# Arduino_40hz_audio_and_led.net
KiCad netlist of a schematic drawn in EAGLE
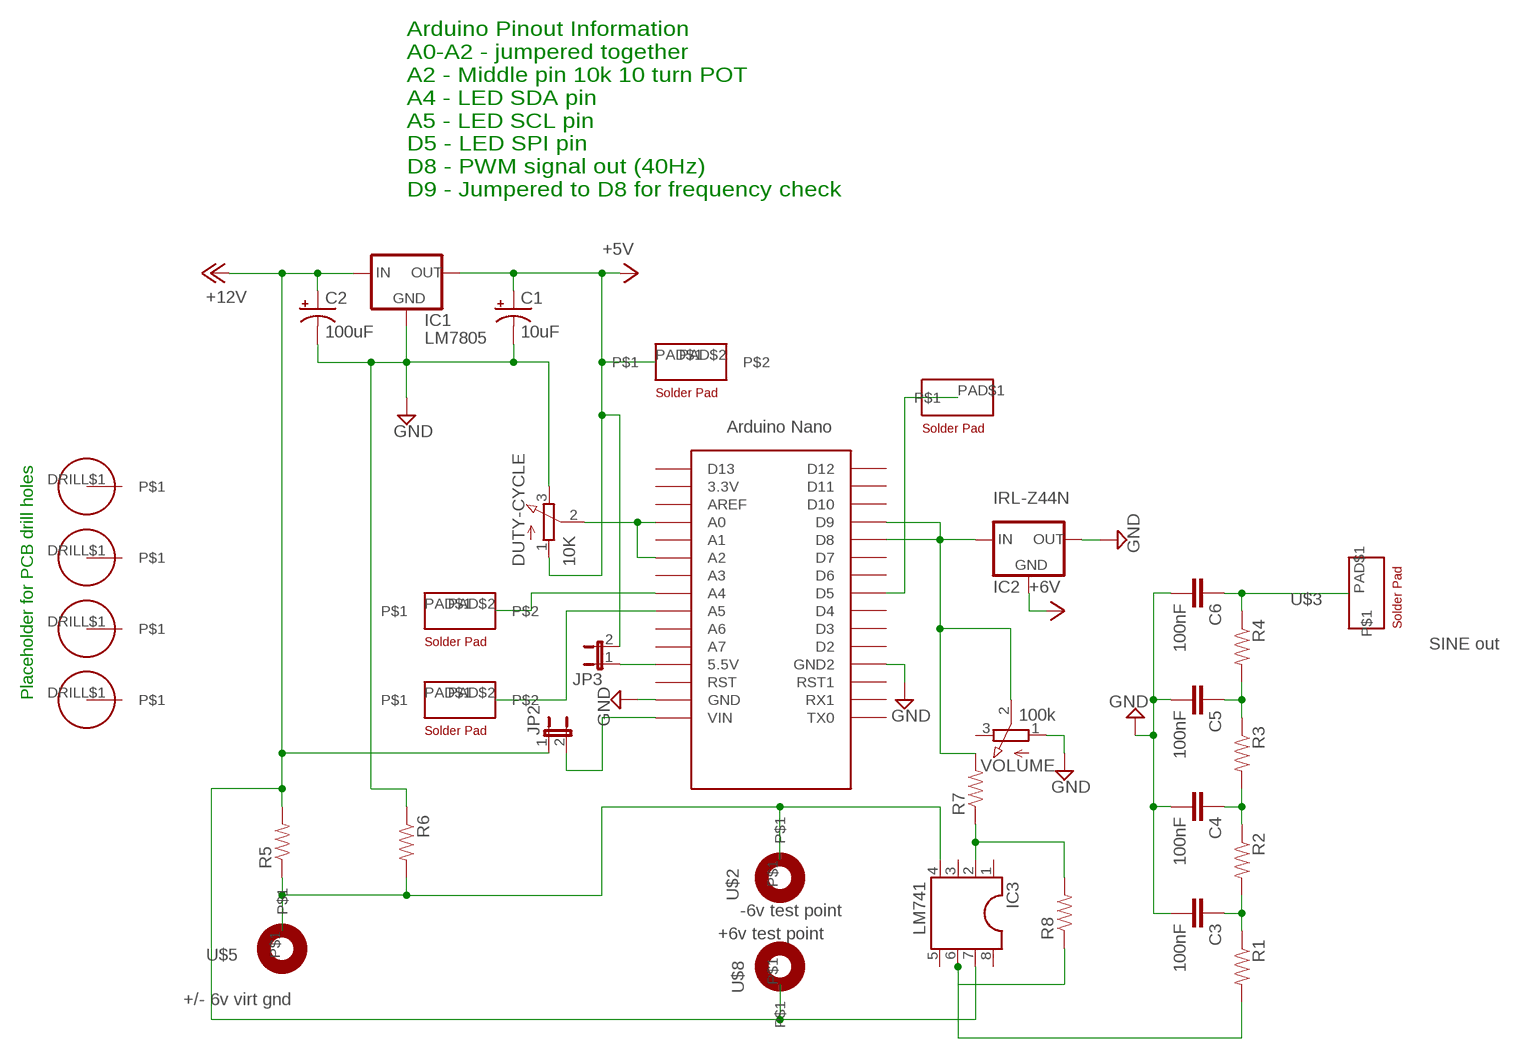
[diagram p0: schematic, sheet 1]

(export (version "E")
  (design (tool "Eeschema 10.0.6"))
  (components
    (comp (ref "C1")
      (value "10uF")
      (footprint "eagle-import:CAP-POLARIZED")
      (libsource (lib "eagle-import") (part "CAP-POLARIZED-RADIAL-2.5MM-25V-20%"))
    )
    (comp (ref "C2")
      (value "100uF")
      (footprint "eagle-import:CAP-POLARIZED")
      (libsource (lib "eagle-import") (part "CAP-POLARIZED-RADIAL-2.5MM-25V-20%"))
    )
    (comp (ref "C3")
      (value "100nF")
      (footprint "eagle-import:CAP-MEDIUM-MUPPET")
      (libsource (lib "eagle-import") (part "CAP-MEDIUM-MUPPET"))
    )
    (comp (ref "C4")
      (value "100nF")
      (footprint "eagle-import:CAP-MEDIUM-MUPPET")
      (libsource (lib "eagle-import") (part "CAP-MEDIUM-MUPPET"))
    )
    (comp (ref "C5")
      (value "100nF")
      (footprint "eagle-import:CAP-MEDIUM-MUPPET")
      (libsource (lib "eagle-import") (part "CAP-MEDIUM-MUPPET"))
    )
    (comp (ref "C6")
      (value "100nF")
      (footprint "eagle-import:CAP-MEDIUM-MUPPET")
      (libsource (lib "eagle-import") (part "CAP-MEDIUM-MUPPET"))
    )
    (comp (ref "DUTY-CYCLE")
      (value "10K")
      (footprint "eagle-import:POTENTIOMETER")
      (libsource (lib "eagle-import") (part "POTENTIOMETER"))
    )
    (comp (ref "IC1")
      (value "LM7805")
      (footprint "eagle-import:78XXL")
      (libsource (lib "eagle-import") (part "V_REG_78XXSIDE"))
    )
    (comp (ref "IC2")
      (value "IRL-Z44N")
      (footprint "eagle-import:78XXL")
      (libsource (lib "eagle-import") (part "V_REG_78XXSIDE"))
    )
    (comp (ref "IC3")
      (value "LM741")
      (footprint "eagle-import:DIL08")
      (libsource (lib "eagle-import") (part "DUAL-INLINE-8DIL08-2"))
    )
    (comp (ref "JP2")
      (value "JUMPER-JP1E")
      (footprint "eagle-import:JP1")
      (libsource (lib "eagle-import") (part "JUMPER-JP1E"))
    )
    (comp (ref "JP3")
      (value "JUMPER-JP1E")
      (footprint "eagle-import:JP1")
      (libsource (lib "eagle-import") (part "JUMPER-JP1E"))
    )
    (comp (ref "P+1")
      (value "+12V")
      (footprint "eagle-import:POWER-IN-PAD")
      (libsource (lib "eagle-import") (part "+12V"))
    )
    (comp (ref "P+2")
      (value "+5V")
      (footprint "eagle-import:POWER-IN-PAD")
      (libsource (lib "eagle-import") (part "+5V"))
    )
    (comp (ref "P+3")
      (value "+6V")
      (footprint "eagle-import:POWER-IN-PAD")
      (libsource (lib "eagle-import") (part "+6V"))
    )
    (comp (ref "R1")
      (value "RESISTORPTH-1/4W")
      (footprint "eagle-import:AXIAL-0.4")
      (libsource (lib "eagle-import") (part "RESISTORPTH-1/4W"))
    )
    (comp (ref "R2")
      (value "RESISTORPTH-1/4W")
      (footprint "eagle-import:AXIAL-0.4")
      (libsource (lib "eagle-import") (part "RESISTORPTH-1/4W"))
    )
    (comp (ref "R3")
      (value "RESISTORPTH-1/4W")
      (footprint "eagle-import:AXIAL-0.4")
      (libsource (lib "eagle-import") (part "RESISTORPTH-1/4W"))
    )
    (comp (ref "R4")
      (value "RESISTORPTH-1/4W")
      (footprint "eagle-import:AXIAL-0.4")
      (libsource (lib "eagle-import") (part "RESISTORPTH-1/4W"))
    )
    (comp (ref "R5")
      (value "RESISTORPTH-1/4W")
      (footprint "eagle-import:AXIAL-0.4")
      (libsource (lib "eagle-import") (part "RESISTORPTH-1/4W"))
    )
    (comp (ref "R6")
      (value "RESISTORPTH-1/4W")
      (footprint "eagle-import:AXIAL-0.4")
      (libsource (lib "eagle-import") (part "RESISTORPTH-1/4W"))
    )
    (comp (ref "R7")
      (value "RESISTORPTH-1/4W")
      (footprint "eagle-import:AXIAL-0.4")
      (libsource (lib "eagle-import") (part "RESISTORPTH-1/4W"))
    )
    (comp (ref "R8")
      (value "RESISTORPTH-1/4W")
      (footprint "eagle-import:AXIAL-0.4")
      (libsource (lib "eagle-import") (part "RESISTORPTH-1/4W"))
    )
    (comp (ref "U$1")
      (value "ARDUINO-NANO")
      (footprint "eagle-import:ARDUINO-NANO")
      (libsource (lib "eagle-import") (part "ARDUINO-NANO"))
    )
    (comp (ref "U$2")
      (value "-6v test point")
      (footprint "eagle-import:PROBE_POINT_1")
      (libsource (lib "eagle-import") (part "PROBE-POINTPROBE_POINT_1"))
    )
    (comp (ref "U$3")
      (value "SINE out")
      (footprint "eagle-import:PAD-1PIN-RECTANGLE-125MIL")
      (libsource (lib "eagle-import") (part "PAD-1PIN-RECTANGLE"))
    )
    (comp (ref "U$4")
      (value "PAD-2PIN-RECTANGLE")
      (footprint "eagle-import:PAD-2PIN-RECTANGLE-50MIL")
      (libsource (lib "eagle-import") (part "PAD-2PIN-RECTANGLE"))
    )
    (comp (ref "U$5")
      (value "+/- 6v virt gnd")
      (footprint "eagle-import:PROBE_POINT_1")
      (libsource (lib "eagle-import") (part "PROBE-POINTPROBE_POINT_1"))
    )
    (comp (ref "U$6")
      (value "PAD-2PIN-RECTANGLE")
      (footprint "eagle-import:PAD-2PIN-RECTANGLE-50MIL")
      (libsource (lib "eagle-import") (part "PAD-2PIN-RECTANGLE"))
    )
    (comp (ref "U$7")
      (value "PAD-2PIN-RECTANGLE")
      (footprint "eagle-import:PAD-2PIN-RECTANGLE-50MIL")
      (libsource (lib "eagle-import") (part "PAD-2PIN-RECTANGLE"))
    )
    (comp (ref "U$8")
      (value "+6v test point")
      (footprint "eagle-import:PROBE_POINT_1")
      (libsource (lib "eagle-import") (part "PROBE-POINTPROBE_POINT_1"))
    )
    (comp (ref "U$9")
      (value "PAD-1PIN-RECTANGLE")
      (footprint "eagle-import:PAD-1PIN-RECTANGLE-125MIL")
      (libsource (lib "eagle-import") (part "PAD-1PIN-RECTANGLE"))
    )
    (comp (ref "U$10")
      (value "DRILL-HOLE-4MM")
      (footprint "eagle-import:DRILL-HOLE-4MM")
      (libsource (lib "eagle-import") (part "DRILL-HOLE-4MM"))
    )
    (comp (ref "U$11")
      (value "DRILL-HOLE-4MM")
      (footprint "eagle-import:DRILL-HOLE-4MM")
      (libsource (lib "eagle-import") (part "DRILL-HOLE-4MM"))
    )
    (comp (ref "U$12")
      (value "DRILL-HOLE-4MM")
      (footprint "eagle-import:DRILL-HOLE-4MM")
      (libsource (lib "eagle-import") (part "DRILL-HOLE-4MM"))
    )
    (comp (ref "U$13")
      (value "DRILL-HOLE-4MM")
      (footprint "eagle-import:DRILL-HOLE-4MM")
      (libsource (lib "eagle-import") (part "DRILL-HOLE-4MM"))
    )
    (comp (ref "VOLUME")
      (value "100k")
      (footprint "eagle-import:POTENTIOMETER")
      (libsource (lib "eagle-import") (part "POTENTIOMETER"))
    )
  )
  (nets
    (net (code "1") (name "+5V") (class "Default")
      (node (ref "C1") (pin "1") (pinfunction "+_1") (pintype "passive"))
      (node (ref "DUTY-CYCLE") (pin "1") (pinfunction "A_1") (pintype "passive"))
      (node (ref "IC1") (pin "OUT") (pinfunction "OUT_OUT") (pintype "output"))
      (node (ref "IC2") (pin "GND") (pinfunction "GND_GND") (pintype "input"))
      (node (ref "JP3") (pin "2") (pinfunction "2_2") (pintype "passive"))
      (node (ref "P+2") (pin "VCC") (pinfunction "+5V_VCC") (pintype "power_in"))
      (node (ref "P+3") (pin "VCC") (pinfunction "+5V_VCC") (pintype "power_in"))
      (node (ref "U$7") (pin "PAD$1") (pinfunction "P$1_PAD$1") (pintype "bidirectional"))
    )
    (net (code "2") (name "+12V") (class "Default")
      (node (ref "C2") (pin "1") (pinfunction "+_1") (pintype "passive"))
      (node (ref "IC1") (pin "IN") (pinfunction "IN_IN") (pintype "input"))
      (node (ref "IC3") (pin "7") (pinfunction "7_7") (pintype "passive"))
      (node (ref "JP2") (pin "1") (pinfunction "1_1") (pintype "passive"))
      (node (ref "P+1") (pin "VCC") (pinfunction "+12V_VCC") (pintype "power_in"))
      (node (ref "R5") (pin "P$2") (pinfunction "2_P$2") (pintype "passive"))
      (node (ref "U$8") (pin "P$1") (pinfunction "P$1_P$1") (pintype "bidirectional"))
    )
    (net (code "3") (name "GND") (class "Default")
      (node (ref "C1") (pin "2") (pinfunction "-_2") (pintype "passive"))
      (node (ref "C2") (pin "2") (pinfunction "-_2") (pintype "passive"))
      (node (ref "C3") (pin "2") (pinfunction "2_2") (pintype "passive"))
      (node (ref "C4") (pin "2") (pinfunction "2_2") (pintype "passive"))
      (node (ref "C5") (pin "2") (pinfunction "2_2") (pintype "passive"))
      (node (ref "C6") (pin "2") (pinfunction "2_2") (pintype "passive"))
      (node (ref "DUTY-CYCLE") (pin "3") (pinfunction "E_3") (pintype "passive"))
      (node (ref "IC1") (pin "GND") (pinfunction "GND_GND") (pintype "input"))
      (node (ref "IC2") (pin "OUT") (pinfunction "OUT_OUT") (pintype "output"))
      (node (ref "R6") (pin "P$1") (pinfunction "1_P$1") (pintype "passive"))
      (node (ref "U$1") (pin "GND") (pinfunction "GND_GND") (pintype "bidirectional"))
      (node (ref "U$1") (pin "GND1") (pinfunction "GND2_GND1") (pintype "bidirectional"))
      (node (ref "VOLUME") (pin "1") (pinfunction "A_1") (pintype "passive"))
    )
    (net (code "4") (name "Net-(DUTY-CYCLE-S)") (class "Default")
      (node (ref "DUTY-CYCLE") (pin "2") (pinfunction "S_2") (pintype "passive"))
      (node (ref "U$1") (pin "A0") (pinfunction "A0_A0") (pintype "bidirectional"))
      (node (ref "U$1") (pin "A2") (pinfunction "A2_A2") (pintype "bidirectional"))
    )
    (net (code "5") (name "Net-(R1-1)") (class "Default")
      (node (ref "C3") (pin "1") (pinfunction "1_1") (pintype "passive"))
      (node (ref "R1") (pin "P$1") (pinfunction "1_P$1") (pintype "passive"))
      (node (ref "R2") (pin "P$2") (pinfunction "2_P$2") (pintype "passive"))
    )
    (net (code "6") (name "Net-(R1-2)") (class "Default")
      (node (ref "IC3") (pin "6") (pinfunction "6_6") (pintype "passive"))
      (node (ref "R1") (pin "P$2") (pinfunction "2_P$2") (pintype "passive"))
      (node (ref "R8") (pin "P$1") (pinfunction "1_P$1") (pintype "passive"))
    )
    (net (code "7") (name "Net-(R2-1)") (class "Default")
      (node (ref "C4") (pin "1") (pinfunction "1_1") (pintype "passive"))
      (node (ref "R2") (pin "P$1") (pinfunction "1_P$1") (pintype "passive"))
      (node (ref "R3") (pin "P$2") (pinfunction "2_P$2") (pintype "passive"))
    )
    (net (code "8") (name "Net-(R3-1)") (class "Default")
      (node (ref "C5") (pin "1") (pinfunction "1_1") (pintype "passive"))
      (node (ref "R3") (pin "P$1") (pinfunction "1_P$1") (pintype "passive"))
      (node (ref "R4") (pin "P$2") (pinfunction "2_P$2") (pintype "passive"))
    )
    (net (code "9") (name "Net-(R4-1)") (class "Default")
      (node (ref "C6") (pin "1") (pinfunction "1_1") (pintype "passive"))
      (node (ref "R4") (pin "P$1") (pinfunction "1_P$1") (pintype "passive"))
    )
    (net (code "10") (name "Net-(R5-1)") (class "Default")
      (node (ref "IC3") (pin "4") (pinfunction "4_4") (pintype "passive"))
      (node (ref "R5") (pin "P$1") (pinfunction "1_P$1") (pintype "passive"))
      (node (ref "R6") (pin "P$2") (pinfunction "2_P$2") (pintype "passive"))
      (node (ref "U$2") (pin "P$1") (pinfunction "P$1_P$1") (pintype "bidirectional"))
      (node (ref "U$5") (pin "P$1") (pinfunction "P$1_P$1") (pintype "bidirectional"))
    )
    (net (code "11") (name "Net-(R7-1)") (class "Default")
      (node (ref "IC3") (pin "2") (pinfunction "2_2") (pintype "passive"))
      (node (ref "R7") (pin "P$1") (pinfunction "1_P$1") (pintype "passive"))
      (node (ref "R8") (pin "P$2") (pinfunction "2_P$2") (pintype "passive"))
    )
    (net (code "12") (name "Net-(R7-2)") (class "Default")
      (node (ref "IC2") (pin "IN") (pinfunction "IN_IN") (pintype "input"))
      (node (ref "R7") (pin "P$2") (pinfunction "2_P$2") (pintype "passive"))
      (node (ref "U$1") (pin "D8") (pinfunction "D8_D8") (pintype "bidirectional"))
      (node (ref "U$1") (pin "D9") (pinfunction "D9_D9") (pintype "bidirectional"))
      (node (ref "VOLUME") (pin "2") (pinfunction "S_2") (pintype "passive"))
    )
    (net (code "13") (name "Net-(U$1-5.5V)") (class "Default")
      (node (ref "JP3") (pin "1") (pinfunction "1_1") (pintype "passive"))
      (node (ref "U$1") (pin "5V") (pinfunction "5.5V_5V") (pintype "bidirectional"))
    )
    (net (code "14") (name "Net-(U$1-VIN)") (class "Default")
      (node (ref "JP2") (pin "2") (pinfunction "2_2") (pintype "passive"))
      (node (ref "U$1") (pin "RAW") (pinfunction "VIN_RAW") (pintype "bidirectional"))
    )
    (net (code "15") (name "Net-(U$4-P$2)") (class "Default")
      (node (ref "U$1") (pin "A4") (pinfunction "A4_A4") (pintype "bidirectional"))
      (node (ref "U$4") (pin "PAD$2") (pinfunction "P$2_PAD$2") (pintype "bidirectional"))
    )
    (net (code "16") (name "Net-(U$6-P$2)") (class "Default")
      (node (ref "U$1") (pin "A5") (pinfunction "A5_A5") (pintype "bidirectional"))
      (node (ref "U$6") (pin "PAD$2") (pinfunction "P$2_PAD$2") (pintype "bidirectional"))
    )
    (net (code "17") (name "Net-(U$9-P$1)") (class "Default")
      (node (ref "U$1") (pin "D5") (pinfunction "D5_D5") (pintype "bidirectional"))
      (node (ref "U$9") (pin "PAD$1") (pinfunction "P$1_PAD$1") (pintype "bidirectional"))
    )
    (net (code "18") (name "unconnected-(IC3-Pad1)") (class "Default")
      (node (ref "IC3") (pin "1") (pinfunction "1_1") (pintype "passive"))
    )
    (net (code "19") (name "unconnected-(IC3-Pad3)") (class "Default")
      (node (ref "IC3") (pin "3") (pinfunction "3_3") (pintype "passive"))
    )
    (net (code "20") (name "unconnected-(IC3-Pad5)") (class "Default")
      (node (ref "IC3") (pin "5") (pinfunction "5_5") (pintype "passive"))
    )
    (net (code "21") (name "unconnected-(IC3-Pad8)") (class "Default")
      (node (ref "IC3") (pin "8") (pinfunction "8_8") (pintype "passive"))
    )
    (net (code "22") (name "unconnected-(U$1-Pad3.3V)") (class "Default")
      (node (ref "U$1") (pin "3.3V") (pinfunction "3.3V_3.3V") (pintype "bidirectional"))
    )
    (net (code "23") (name "unconnected-(U$1-PadA1)") (class "Default")
      (node (ref "U$1") (pin "A1") (pinfunction "A1_A1") (pintype "bidirectional"))
    )
    (net (code "24") (name "unconnected-(U$1-PadA3)") (class "Default")
      (node (ref "U$1") (pin "A3") (pinfunction "A3_A3") (pintype "bidirectional"))
    )
    (net (code "25") (name "unconnected-(U$1-PadA6)") (class "Default")
      (node (ref "U$1") (pin "A6") (pinfunction "A6_A6") (pintype "bidirectional"))
    )
    (net (code "26") (name "unconnected-(U$1-PadA7)") (class "Default")
      (node (ref "U$1") (pin "A7") (pinfunction "A7_A7") (pintype "bidirectional"))
    )
    (net (code "27") (name "unconnected-(U$1-PadAREF)") (class "Default")
      (node (ref "U$1") (pin "AREF") (pinfunction "AREF_AREF") (pintype "bidirectional"))
    )
    (net (code "28") (name "unconnected-(U$1-PadD2)") (class "Default")
      (node (ref "U$1") (pin "D2") (pinfunction "D2_D2") (pintype "bidirectional"))
    )
    (net (code "29") (name "unconnected-(U$1-PadD3)") (class "Default")
      (node (ref "U$1") (pin "D3") (pinfunction "D3_D3") (pintype "bidirectional"))
    )
    (net (code "30") (name "unconnected-(U$1-PadD4)") (class "Default")
      (node (ref "U$1") (pin "D4") (pinfunction "D4_D4") (pintype "bidirectional"))
    )
    (net (code "31") (name "unconnected-(U$1-PadD6)") (class "Default")
      (node (ref "U$1") (pin "D6") (pinfunction "D6_D6") (pintype "bidirectional"))
    )
    (net (code "32") (name "unconnected-(U$1-PadD7)") (class "Default")
      (node (ref "U$1") (pin "D7") (pinfunction "D7_D7") (pintype "bidirectional"))
    )
    (net (code "33") (name "unconnected-(U$1-PadD10)") (class "Default")
      (node (ref "U$1") (pin "D10") (pinfunction "D10_D10") (pintype "bidirectional"))
    )
    (net (code "34") (name "unconnected-(U$1-PadD11)") (class "Default")
      (node (ref "U$1") (pin "D11") (pinfunction "D11_D11") (pintype "bidirectional"))
    )
    (net (code "35") (name "unconnected-(U$1-PadD12)") (class "Default")
      (node (ref "U$1") (pin "D12") (pinfunction "D12_D12") (pintype "bidirectional"))
    )
    (net (code "36") (name "unconnected-(U$1-PadD13)") (class "Default")
      (node (ref "U$1") (pin "D13") (pinfunction "D13_D13") (pintype "bidirectional"))
    )
    (net (code "37") (name "unconnected-(U$1-PadRST)") (class "Default")
      (node (ref "U$1") (pin "RST") (pinfunction "RST_RST") (pintype "bidirectional"))
    )
    (net (code "38") (name "unconnected-(U$1-PadRST1)") (class "Default")
      (node (ref "U$1") (pin "RST1") (pinfunction "RST1_RST1") (pintype "bidirectional"))
    )
    (net (code "39") (name "unconnected-(U$1-PadRX1)") (class "Default")
      (node (ref "U$1") (pin "RX1") (pinfunction "RX1_RX1") (pintype "bidirectional"))
    )
    (net (code "40") (name "unconnected-(U$1-PadTX0)") (class "Default")
      (node (ref "U$1") (pin "TX0") (pinfunction "TX0_TX0") (pintype "bidirectional"))
    )
    (net (code "41") (name "unconnected-(U$3-P$1-PadPAD$1)") (class "Default")
      (node (ref "U$3") (pin "PAD$1") (pinfunction "P$1_PAD$1") (pintype "bidirectional"))
    )
    (net (code "42") (name "unconnected-(U$4-P$1-PadPAD$1)") (class "Default")
      (node (ref "U$4") (pin "PAD$1") (pinfunction "P$1_PAD$1") (pintype "bidirectional"))
    )
    (net (code "43") (name "unconnected-(U$6-P$1-PadPAD$1)") (class "Default")
      (node (ref "U$6") (pin "PAD$1") (pinfunction "P$1_PAD$1") (pintype "bidirectional"))
    )
    (net (code "44") (name "unconnected-(U$7-P$2-PadPAD$2)") (class "Default")
      (node (ref "U$7") (pin "PAD$2") (pinfunction "P$2_PAD$2") (pintype "bidirectional"))
    )
    (net (code "45") (name "unconnected-(U$10-P$1-PadDRILL$1)") (class "Default")
      (node (ref "U$10") (pin "DRILL$1") (pinfunction "P$1_DRILL$1") (pintype "bidirectional"))
    )
    (net (code "46") (name "unconnected-(U$11-P$1-PadDRILL$1)") (class "Default")
      (node (ref "U$11") (pin "DRILL$1") (pinfunction "P$1_DRILL$1") (pintype "bidirectional"))
    )
    (net (code "47") (name "unconnected-(U$12-P$1-PadDRILL$1)") (class "Default")
      (node (ref "U$12") (pin "DRILL$1") (pinfunction "P$1_DRILL$1") (pintype "bidirectional"))
    )
    (net (code "48") (name "unconnected-(U$13-P$1-PadDRILL$1)") (class "Default")
      (node (ref "U$13") (pin "DRILL$1") (pinfunction "P$1_DRILL$1") (pintype "bidirectional"))
    )
    (net (code "49") (name "unconnected-(VOLUME-E-Pad3)") (class "Default")
      (node (ref "VOLUME") (pin "3") (pinfunction "E_3") (pintype "passive"))
    )
  )
)
